# Vector_Body_Board_Schematic.net
KiCad netlist of a schematic drawn in EasyEDA
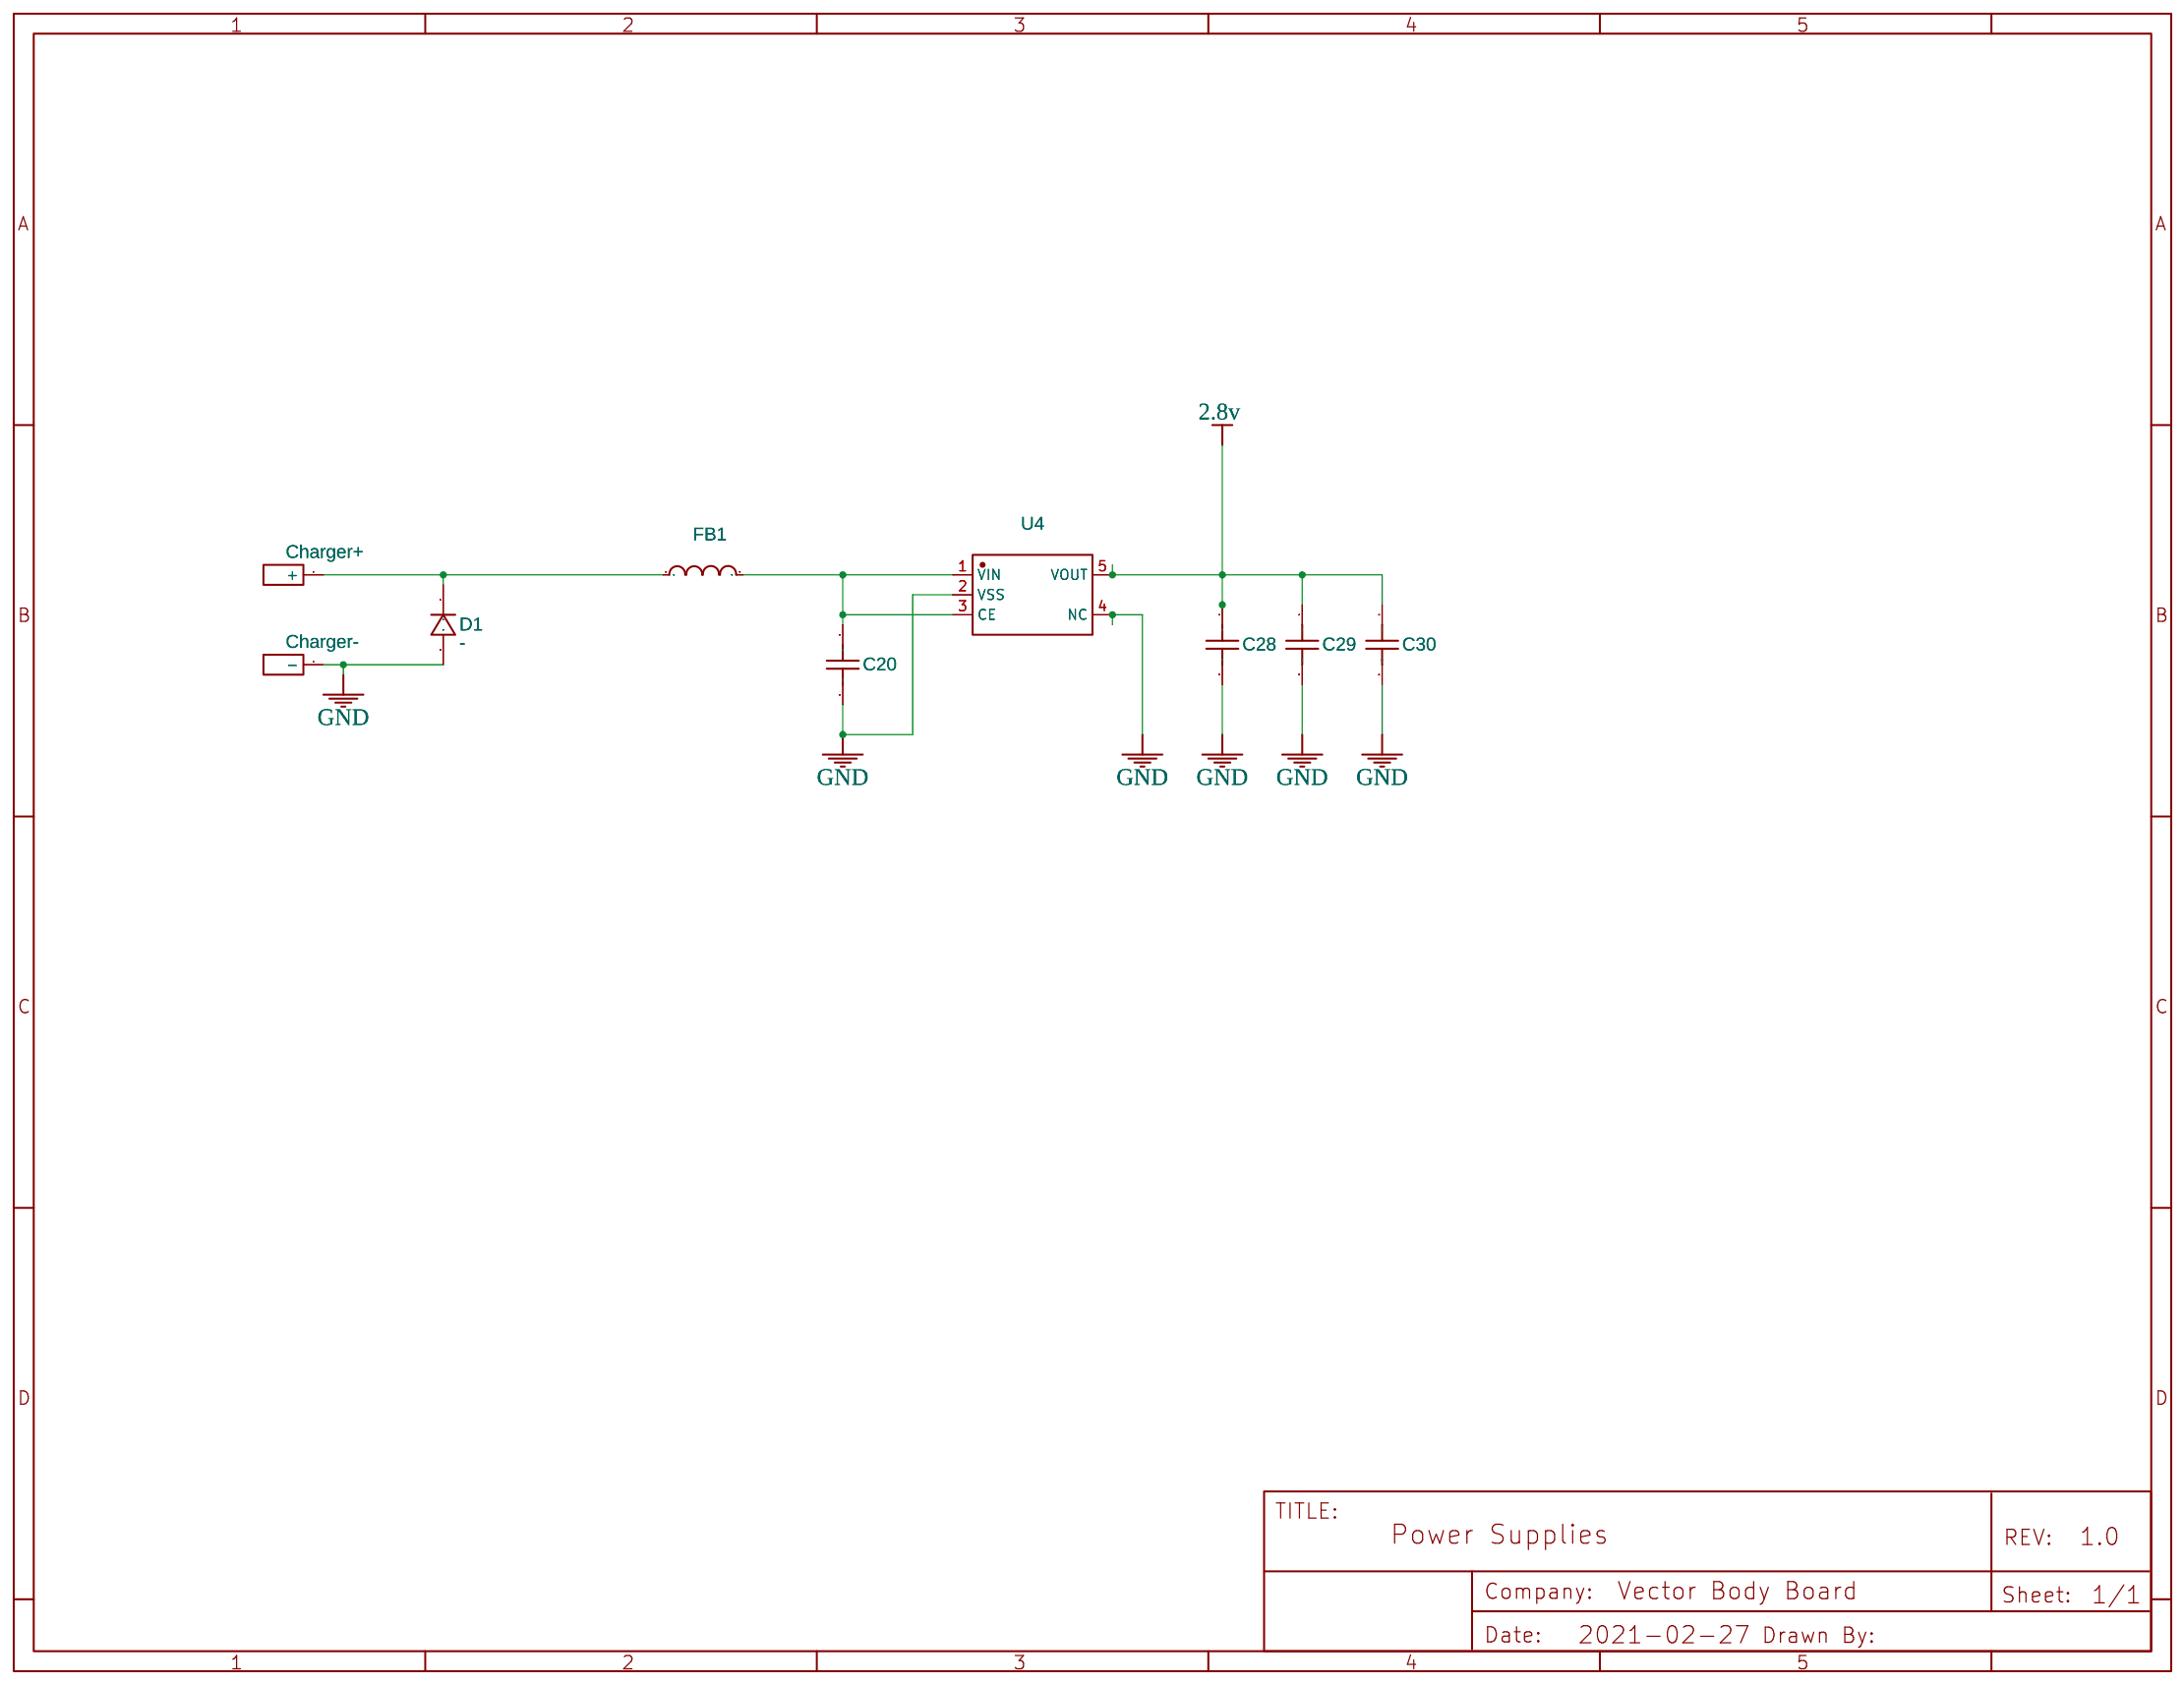
[diagram p0: Power Supply]
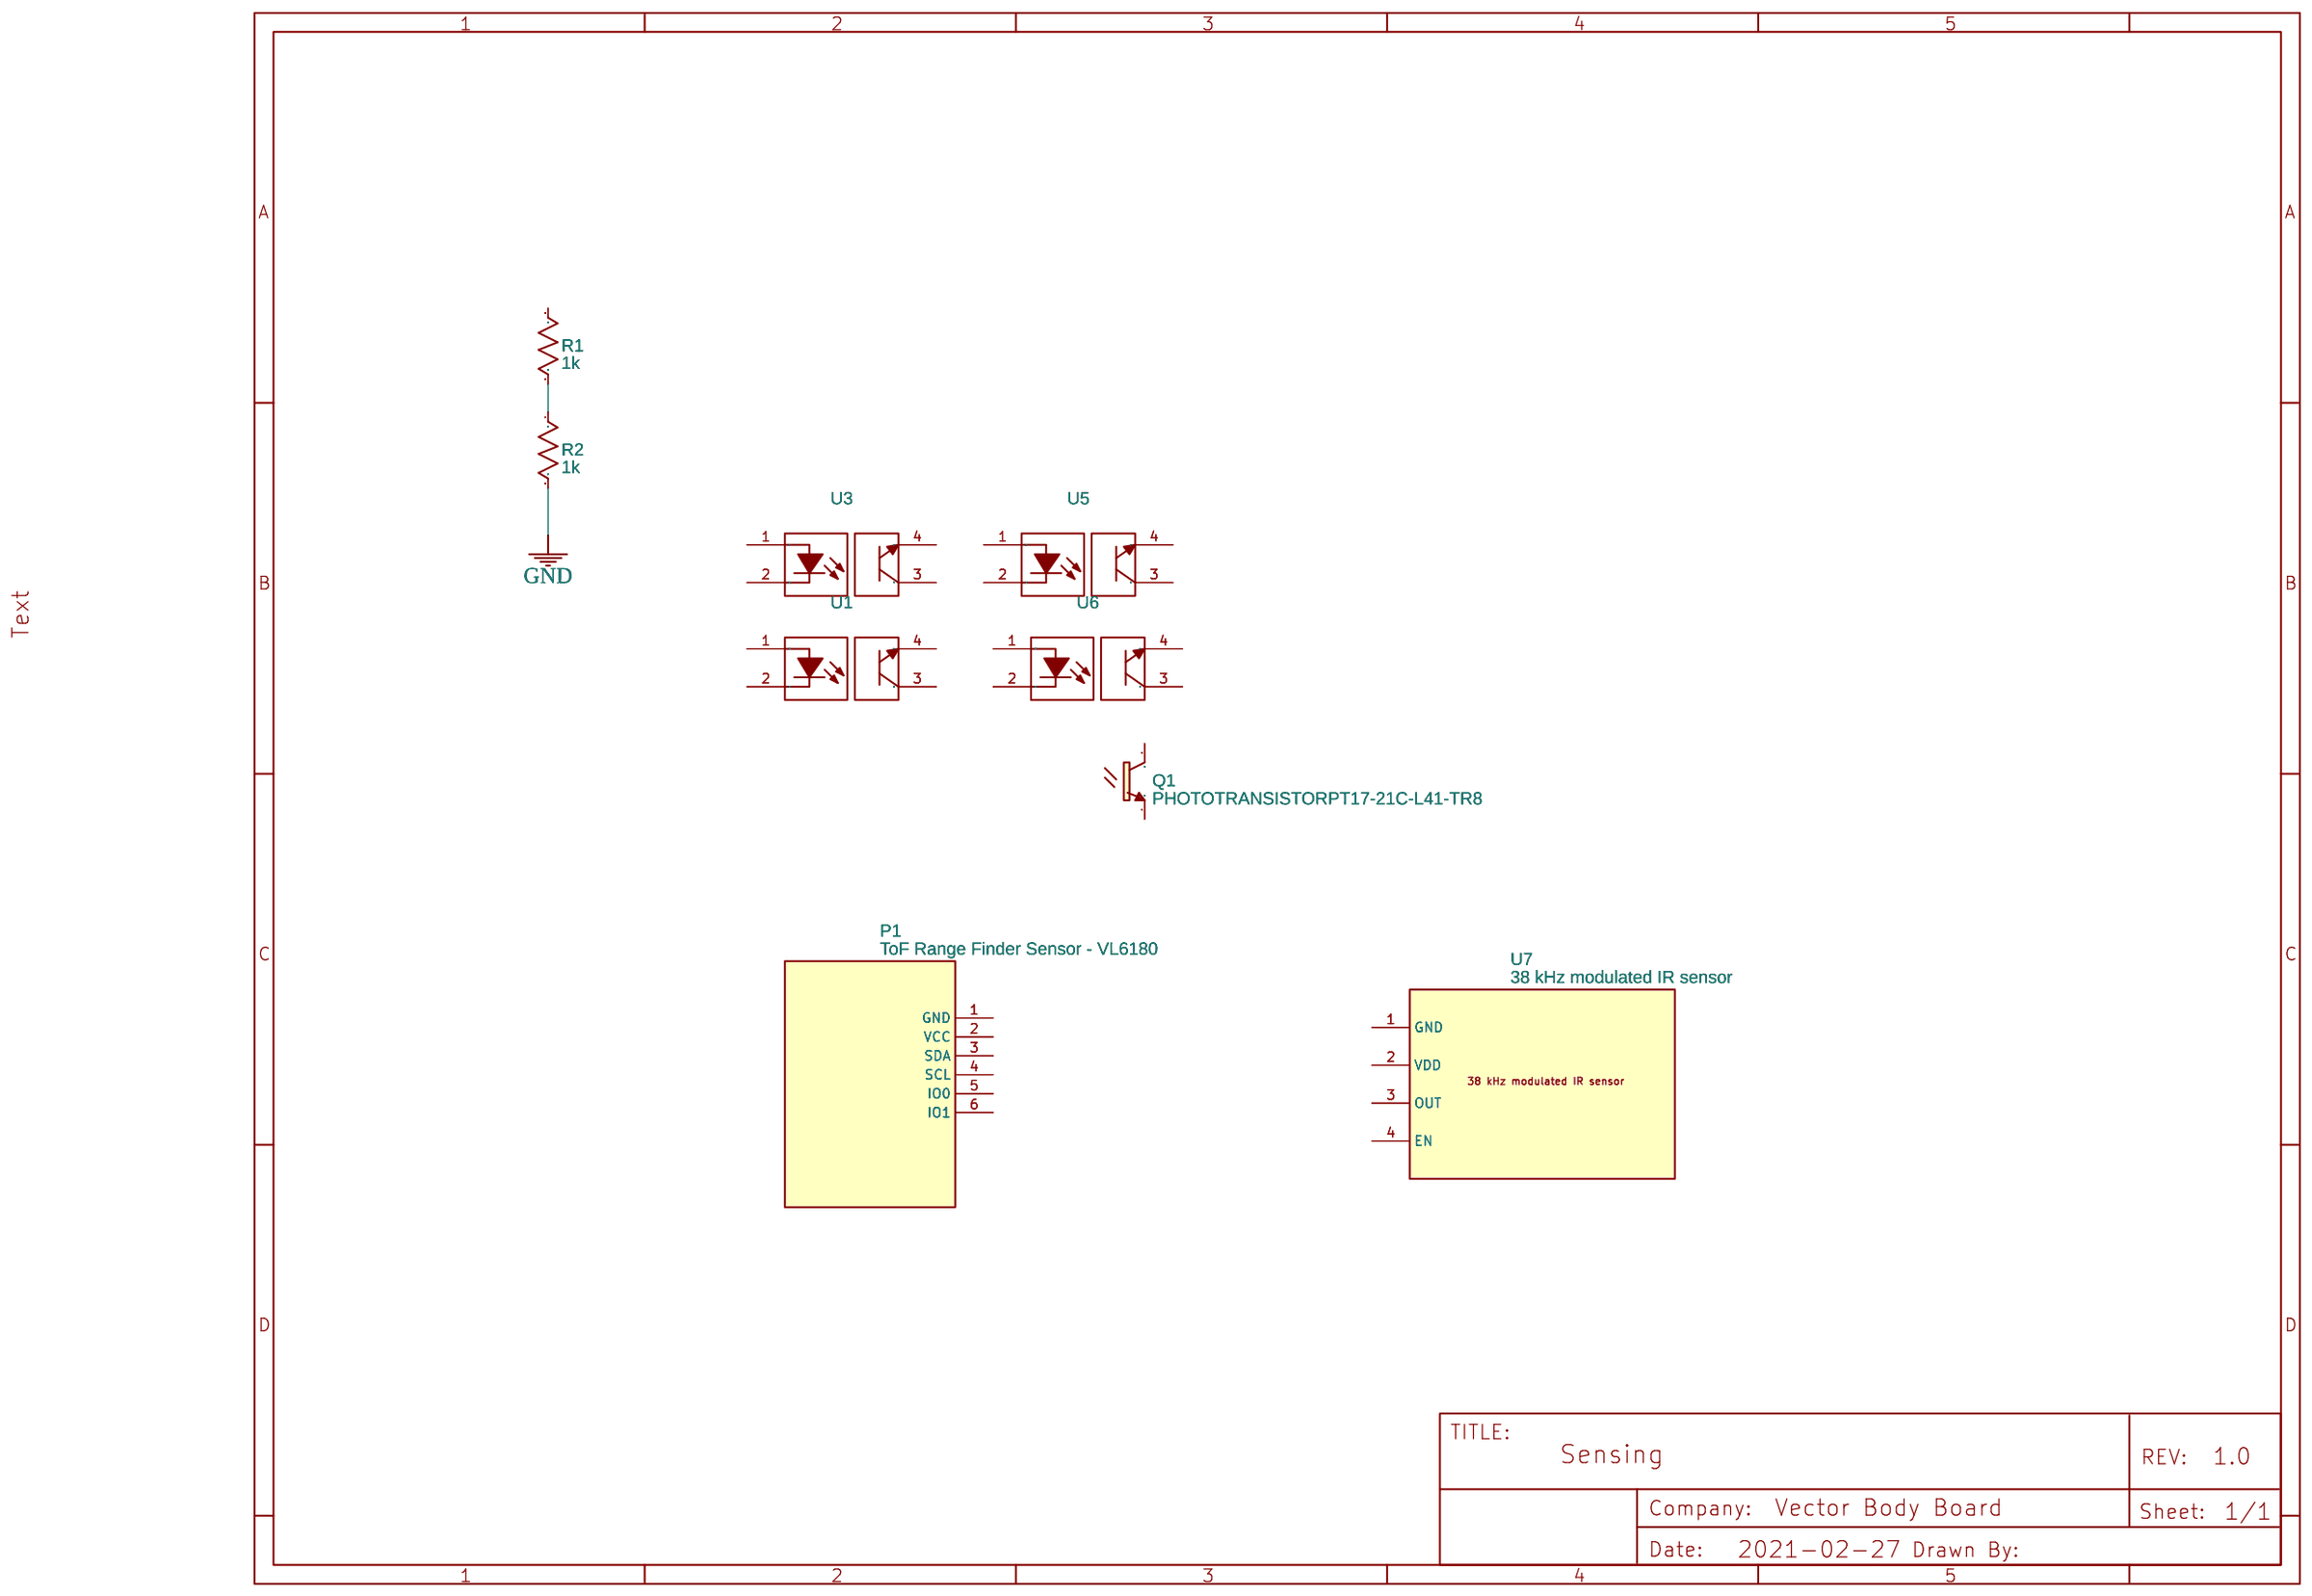
[diagram p1: Sensing]
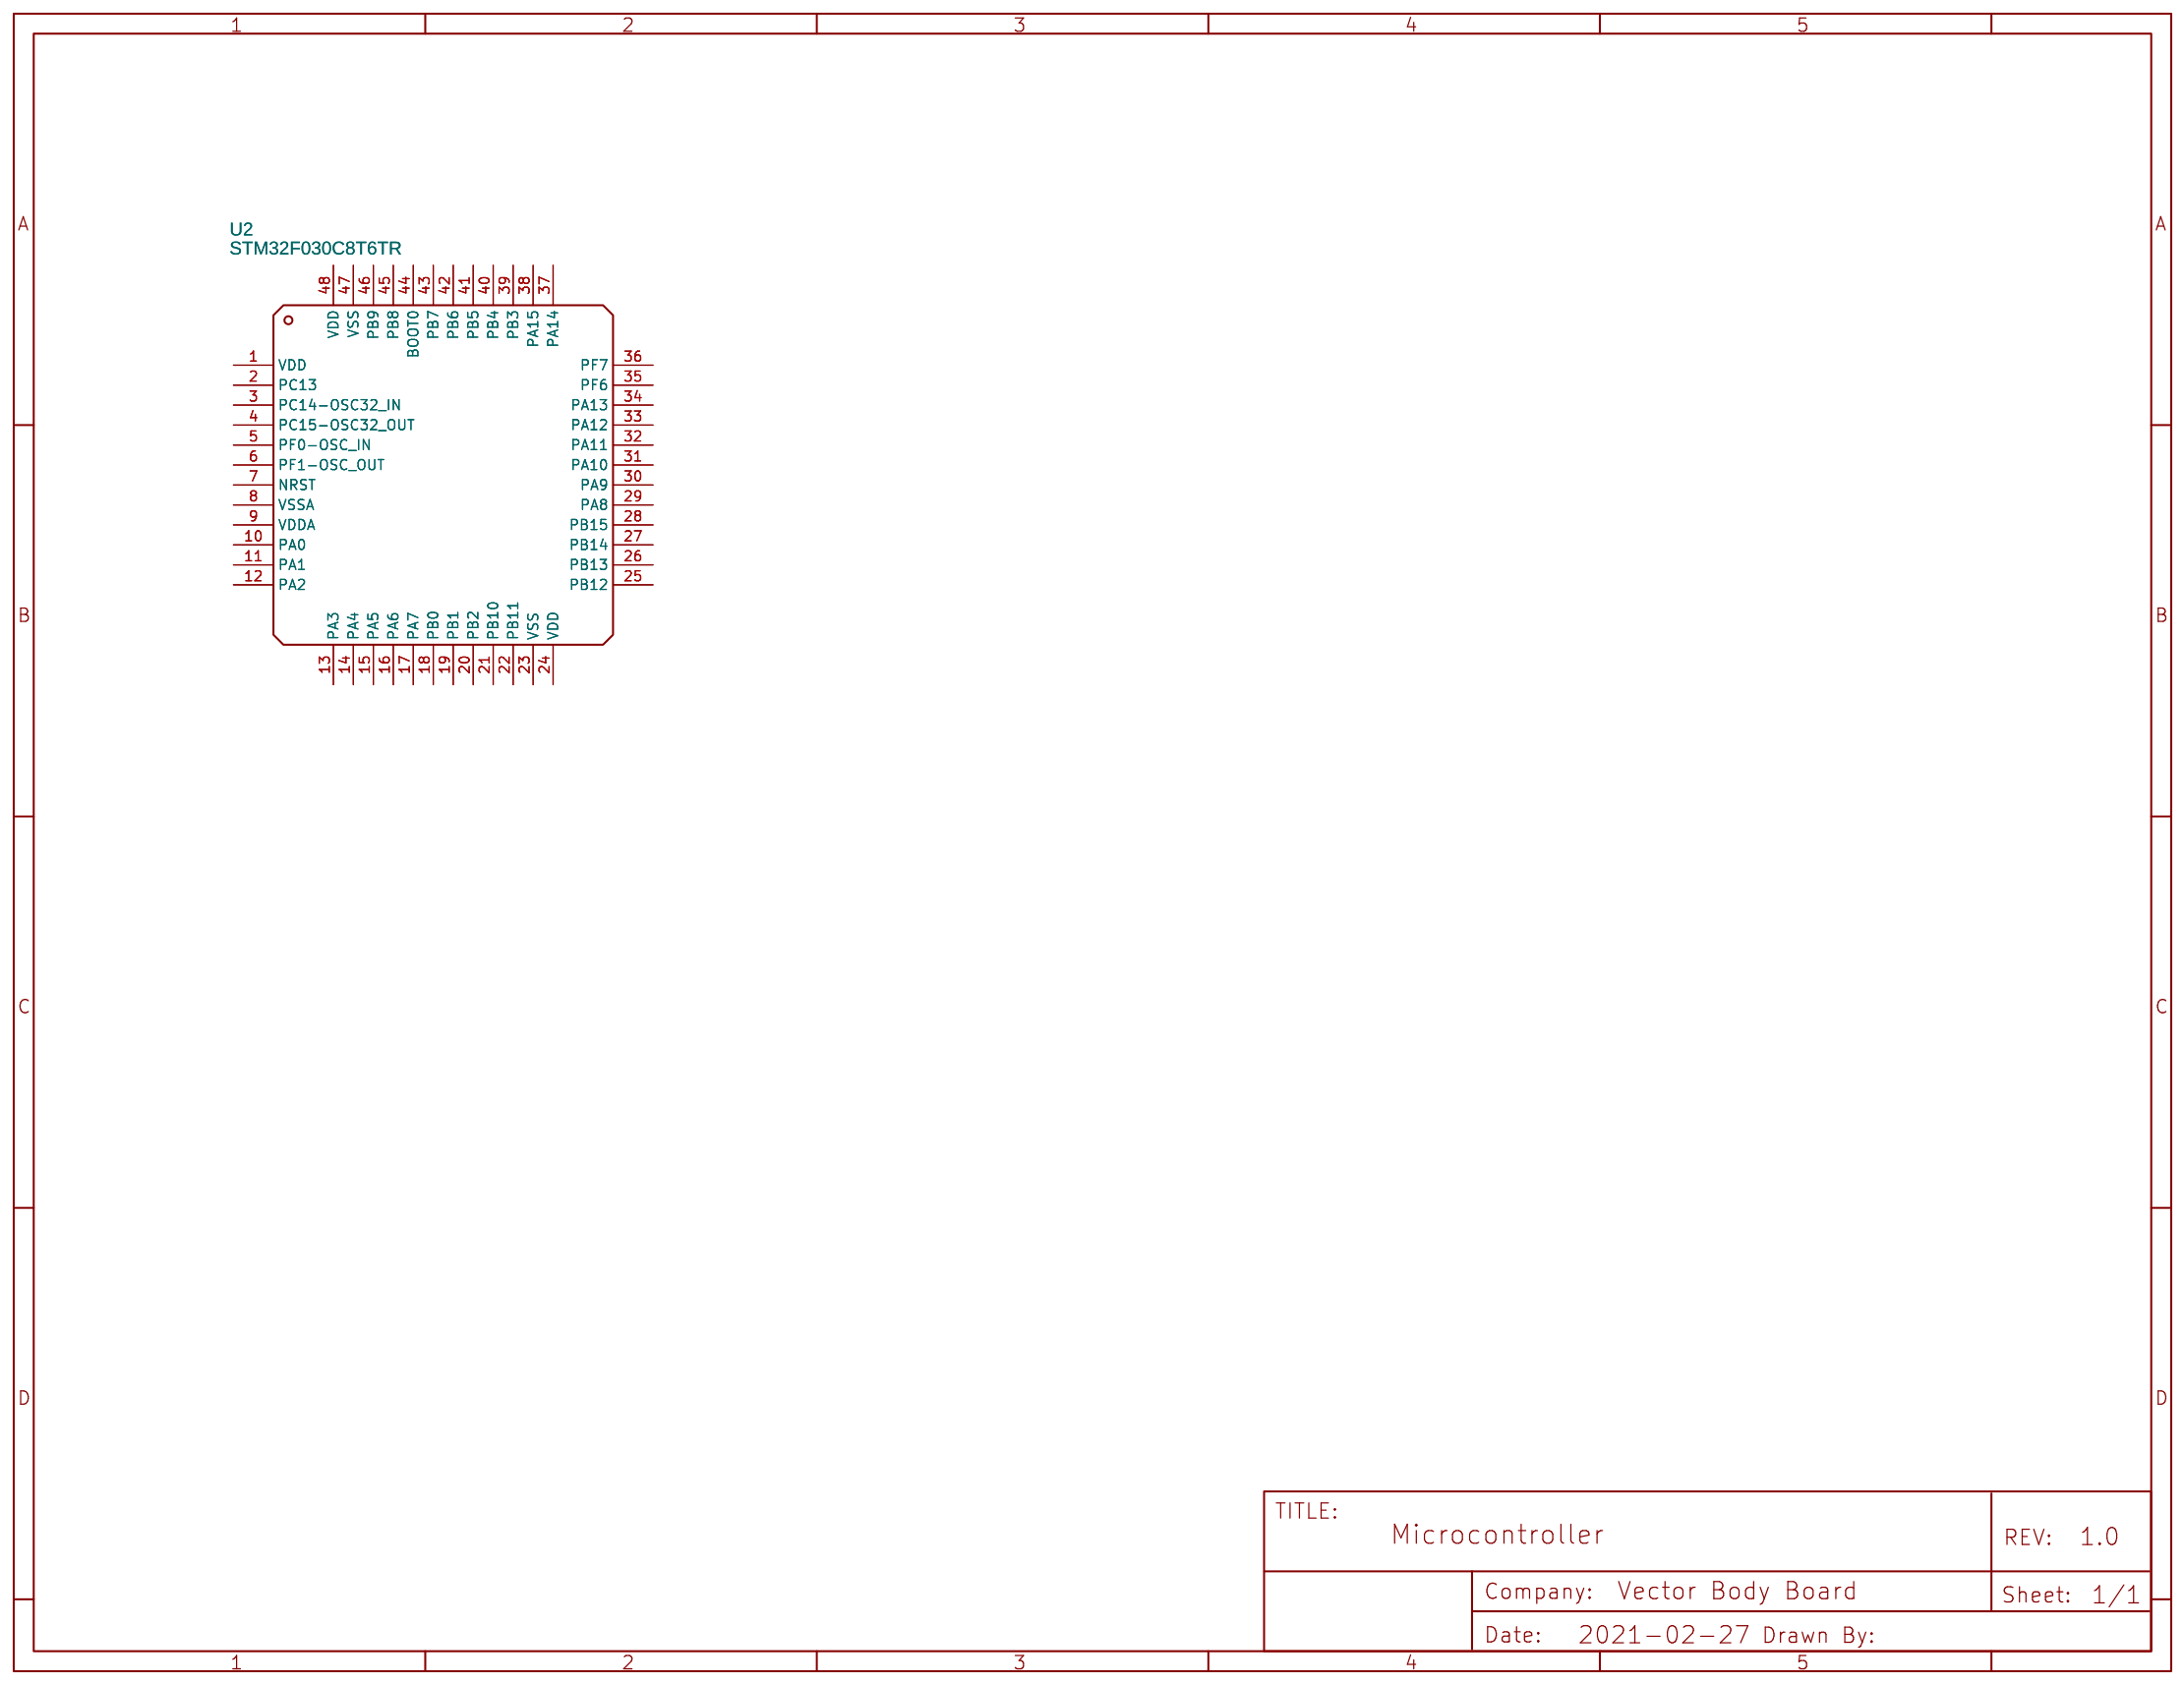
[diagram p2: Microcontroller]

(export (version "E")
  (design (tool "Eeschema 10.0.6"))
  (components
    (comp (ref "+")
      (value "Charger+")
      (fields (field (name "BOM_Supplier Part") "C81276"))
      (libsource (lib "") (part "HDR-M-2.54_1x1"))
    )
    (comp (ref "C20") (value "1u") (libsource (lib "") (part "C_0603_US")))
    (comp (ref "C28") (value "0.1u") (libsource (lib "") (part "C_0603_US")))
    (comp (ref "C29") (value "0.1u") (libsource (lib "") (part "C_0603_US")))
    (comp (ref "C30") (value "0.1u") (libsource (lib "") (part "C_0603_US")))
    (comp (ref "D1")
      (value "-")
      (fields (field (name "BOM_Manufacturer Part") "1N4007W") (field (name "BOM_Supplier Part") "C328592"))
      (libsource (lib "") (part "1N4007W"))
    )
    (comp (ref "FB1")
      (value "Straight-through")
      (fields
        (field (name "BOM_Manufacturer Part") "Straight-through beads")
        (field (name "BOM_Supplier Part") "C46030")
      )
      (libsource (lib "") (part "Straight-through beads"))
    )
    (comp (ref "J2") (value "Charger-") (libsource (lib "") (part "HDR-M-2.54_1x1_1")))
    (comp (ref "U4")
      (value "XC6204B282MR")
      (fields (field (name "BOM_Supplier Part") "C17012"))
      (libsource (lib "") (part "XC6204B282MR"))
    )
    (comp (ref "P1")
      (value "ToF Range Finder Sensor - VL6180")
      (fields (field (name "BOM_Supplier Part") "12587"))
      (libsource (lib "") (part "ToF Range Finder Sensor - VL6180"))
    )
    (comp (ref "Q1")
      (value "PHOTOTRANSISTORPT17-21C-L41-TR8")
      (libsource (lib "") (part "PHOTOTRANSISTORPT17-21C-L41-TR8"))
    )
    (comp (ref "R1") (value "1k") (libsource (lib "") (part "R_0603_US")))
    (comp (ref "R2") (value "1k") (libsource (lib "") (part "R_0603_US")))
    (comp (ref "U1")
      (value "H21A1")
      (fields (field (name "BOM_Supplier Part") "C90607"))
      (libsource (lib "") (part "H21A1"))
    )
    (comp (ref "U3")
      (value "H21A1")
      (fields (field (name "BOM_Supplier Part") "C90607"))
      (libsource (lib "") (part "H21A1"))
    )
    (comp (ref "U5")
      (value "H21A1")
      (fields (field (name "BOM_Supplier Part") "C90607"))
      (libsource (lib "") (part "H21A1"))
    )
    (comp (ref "U6")
      (value "H21A1")
      (fields (field (name "BOM_Supplier Part") "C90607"))
      (libsource (lib "") (part "H21A1"))
    )
    (comp (ref "U7")
      (value "38 kHz modulated IR sensor")
      (libsource (lib "") (part "38 kHz modulated IR sensor"))
    )
    (comp (ref "U2")
      (value "STM32F030C8T6TR")
      (fields (field (name "BOM_Supplier Part") "C40053"))
      (libsource (lib "") (part "STM32F030C8T6TR"))
    )
  )
  (nets
    (net (code "1") (name "2.8v") (class "Default")
      (node (ref "C28") (pin "1") (pinfunction "1_1") (pintype "unspecified"))
      (node (ref "C29") (pin "1") (pinfunction "1_1") (pintype "unspecified"))
      (node (ref "C30") (pin "1") (pinfunction "1_1") (pintype "unspecified"))
      (node (ref "U4") (pin "5") (pinfunction "VOUT_5") (pintype "unspecified"))
    )
    (net (code "2") (name "GND") (class "Default")
      (node (ref "C20") (pin "2") (pinfunction "2_2") (pintype "unspecified"))
      (node (ref "C28") (pin "2") (pinfunction "2_2") (pintype "unspecified"))
      (node (ref "C29") (pin "2") (pinfunction "2_2") (pintype "unspecified"))
      (node (ref "C30") (pin "2") (pinfunction "2_2") (pintype "unspecified"))
      (node (ref "D1") (pin "2") (pinfunction "2_2") (pintype "unspecified"))
      (node (ref "J2") (pin "1") (pinfunction "-_1") (pintype "input"))
      (node (ref "R2") (pin "2") (pinfunction "2_2") (pintype "unspecified"))
      (node (ref "U4") (pin "2") (pinfunction "VSS_2") (pintype "unspecified"))
      (node (ref "U4") (pin "4") (pinfunction "NC_4") (pintype "unspecified"))
    )
    (net (code "3") (name "Net-(+-+)") (class "Default")
      (node (ref "+") (pin "1") (pinfunction "+_1") (pintype "input"))
      (node (ref "D1") (pin "1") (pinfunction "1_1") (pintype "unspecified"))
      (node (ref "FB1") (pin "1") (pinfunction "1_1") (pintype "unspecified"))
    )
    (net (code "4") (name "Net-(R1-Pad2)") (class "Default")
      (node (ref "R1") (pin "2") (pinfunction "2_2") (pintype "unspecified"))
      (node (ref "R2") (pin "1") (pinfunction "1_1") (pintype "unspecified"))
    )
    (net (code "5") (name "Net-(U4-CE)") (class "Default")
      (node (ref "C20") (pin "1") (pinfunction "1_1") (pintype "unspecified"))
      (node (ref "FB1") (pin "2") (pinfunction "2_2") (pintype "unspecified"))
      (node (ref "U4") (pin "1") (pinfunction "VIN_1") (pintype "unspecified"))
      (node (ref "U4") (pin "3") (pinfunction "CE_3") (pintype "unspecified"))
    )
    (net (code "6") (name "unconnected-(P1-GND-Pad1)") (class "Default")
      (node (ref "P1") (pin "1") (pinfunction "GND_1") (pintype "unspecified"))
    )
    (net (code "7") (name "unconnected-(P1-IO0-Pad5)") (class "Default")
      (node (ref "P1") (pin "5") (pinfunction "IO0_5") (pintype "unspecified"))
    )
    (net (code "8") (name "unconnected-(P1-IO1-Pad6)") (class "Default")
      (node (ref "P1") (pin "6") (pinfunction "IO1_6") (pintype "unspecified"))
    )
    (net (code "9") (name "unconnected-(P1-SCL-Pad4)") (class "Default")
      (node (ref "P1") (pin "4") (pinfunction "SCL_4") (pintype "unspecified"))
    )
    (net (code "10") (name "unconnected-(P1-SDA-Pad3)") (class "Default")
      (node (ref "P1") (pin "3") (pinfunction "SDA_3") (pintype "unspecified"))
    )
    (net (code "11") (name "unconnected-(P1-VCC-Pad2)") (class "Default")
      (node (ref "P1") (pin "2") (pinfunction "VCC_2") (pintype "unspecified"))
    )
    (net (code "12") (name "unconnected-(Q1-PadC)") (class "Default")
      (node (ref "Q1") (pin "C") (pinfunction "C_C") (pintype "unspecified"))
    )
    (net (code "13") (name "unconnected-(Q1-PadE)") (class "Default")
      (node (ref "Q1") (pin "E") (pinfunction "E_E") (pintype "unspecified"))
    )
    (net (code "14") (name "unconnected-(R1-Pad1)") (class "Default")
      (node (ref "R1") (pin "1") (pinfunction "1_1") (pintype "unspecified"))
    )
    (net (code "15") (name "unconnected-(U1-Pad1)") (class "Default")
      (node (ref "U1") (pin "1") (pinfunction "1_1") (pintype "unspecified"))
    )
    (net (code "16") (name "unconnected-(U1-Pad2)") (class "Default")
      (node (ref "U1") (pin "2") (pinfunction "2_2") (pintype "unspecified"))
    )
    (net (code "17") (name "unconnected-(U1-Pad3)") (class "Default")
      (node (ref "U1") (pin "3") (pinfunction "3_3") (pintype "unspecified"))
    )
    (net (code "18") (name "unconnected-(U1-Pad4)") (class "Default")
      (node (ref "U1") (pin "4") (pinfunction "4_4") (pintype "unspecified"))
    )
    (net (code "19") (name "unconnected-(U2-BOOT0-Pad44)") (class "Default")
      (node (ref "U2") (pin "44") (pinfunction "BOOT0_44") (pintype "unspecified"))
    )
    (net (code "20") (name "unconnected-(U2-NRST-Pad7)") (class "Default")
      (node (ref "U2") (pin "7") (pinfunction "NRST_7") (pintype "unspecified"))
    )
    (net (code "21") (name "unconnected-(U2-PA0-Pad10)") (class "Default")
      (node (ref "U2") (pin "10") (pinfunction "PA0_10") (pintype "unspecified"))
    )
    (net (code "22") (name "unconnected-(U2-PA1-Pad11)") (class "Default")
      (node (ref "U2") (pin "11") (pinfunction "PA1_11") (pintype "unspecified"))
    )
    (net (code "23") (name "unconnected-(U2-PA2-Pad12)") (class "Default")
      (node (ref "U2") (pin "12") (pinfunction "PA2_12") (pintype "unspecified"))
    )
    (net (code "24") (name "unconnected-(U2-PA3-Pad13)") (class "Default")
      (node (ref "U2") (pin "13") (pinfunction "PA3_13") (pintype "unspecified"))
    )
    (net (code "25") (name "unconnected-(U2-PA4-Pad14)") (class "Default")
      (node (ref "U2") (pin "14") (pinfunction "PA4_14") (pintype "unspecified"))
    )
    (net (code "26") (name "unconnected-(U2-PA5-Pad15)") (class "Default")
      (node (ref "U2") (pin "15") (pinfunction "PA5_15") (pintype "unspecified"))
    )
    (net (code "27") (name "unconnected-(U2-PA6-Pad16)") (class "Default")
      (node (ref "U2") (pin "16") (pinfunction "PA6_16") (pintype "unspecified"))
    )
    (net (code "28") (name "unconnected-(U2-PA7-Pad17)") (class "Default")
      (node (ref "U2") (pin "17") (pinfunction "PA7_17") (pintype "unspecified"))
    )
    (net (code "29") (name "unconnected-(U2-PA8-Pad29)") (class "Default")
      (node (ref "U2") (pin "29") (pinfunction "PA8_29") (pintype "unspecified"))
    )
    (net (code "30") (name "unconnected-(U2-PA9-Pad30)") (class "Default")
      (node (ref "U2") (pin "30") (pinfunction "PA9_30") (pintype "unspecified"))
    )
    (net (code "31") (name "unconnected-(U2-PA10-Pad31)") (class "Default")
      (node (ref "U2") (pin "31") (pinfunction "PA10_31") (pintype "unspecified"))
    )
    (net (code "32") (name "unconnected-(U2-PA11-Pad32)") (class "Default")
      (node (ref "U2") (pin "32") (pinfunction "PA11_32") (pintype "unspecified"))
    )
    (net (code "33") (name "unconnected-(U2-PA12-Pad33)") (class "Default")
      (node (ref "U2") (pin "33") (pinfunction "PA12_33") (pintype "unspecified"))
    )
    (net (code "34") (name "unconnected-(U2-PA13-Pad34)") (class "Default")
      (node (ref "U2") (pin "34") (pinfunction "PA13_34") (pintype "unspecified"))
    )
    (net (code "35") (name "unconnected-(U2-PA14-Pad37)") (class "Default")
      (node (ref "U2") (pin "37") (pinfunction "PA14_37") (pintype "unspecified"))
    )
    (net (code "36") (name "unconnected-(U2-PA15-Pad38)") (class "Default")
      (node (ref "U2") (pin "38") (pinfunction "PA15_38") (pintype "unspecified"))
    )
    (net (code "37") (name "unconnected-(U2-PB0-Pad18)") (class "Default")
      (node (ref "U2") (pin "18") (pinfunction "PB0_18") (pintype "unspecified"))
    )
    (net (code "38") (name "unconnected-(U2-PB1-Pad19)") (class "Default")
      (node (ref "U2") (pin "19") (pinfunction "PB1_19") (pintype "unspecified"))
    )
    (net (code "39") (name "unconnected-(U2-PB2-Pad20)") (class "Default")
      (node (ref "U2") (pin "20") (pinfunction "PB2_20") (pintype "unspecified"))
    )
    (net (code "40") (name "unconnected-(U2-PB3-Pad39)") (class "Default")
      (node (ref "U2") (pin "39") (pinfunction "PB3_39") (pintype "unspecified"))
    )
    (net (code "41") (name "unconnected-(U2-PB4-Pad40)") (class "Default")
      (node (ref "U2") (pin "40") (pinfunction "PB4_40") (pintype "unspecified"))
    )
    (net (code "42") (name "unconnected-(U2-PB5-Pad41)") (class "Default")
      (node (ref "U2") (pin "41") (pinfunction "PB5_41") (pintype "unspecified"))
    )
    (net (code "43") (name "unconnected-(U2-PB6-Pad42)") (class "Default")
      (node (ref "U2") (pin "42") (pinfunction "PB6_42") (pintype "unspecified"))
    )
    (net (code "44") (name "unconnected-(U2-PB7-Pad43)") (class "Default")
      (node (ref "U2") (pin "43") (pinfunction "PB7_43") (pintype "unspecified"))
    )
    (net (code "45") (name "unconnected-(U2-PB8-Pad45)") (class "Default")
      (node (ref "U2") (pin "45") (pinfunction "PB8_45") (pintype "unspecified"))
    )
    (net (code "46") (name "unconnected-(U2-PB9-Pad46)") (class "Default")
      (node (ref "U2") (pin "46") (pinfunction "PB9_46") (pintype "unspecified"))
    )
    (net (code "47") (name "unconnected-(U2-PB10-Pad21)") (class "Default")
      (node (ref "U2") (pin "21") (pinfunction "PB10_21") (pintype "unspecified"))
    )
    (net (code "48") (name "unconnected-(U2-PB11-Pad22)") (class "Default")
      (node (ref "U2") (pin "22") (pinfunction "PB11_22") (pintype "unspecified"))
    )
    (net (code "49") (name "unconnected-(U2-PB12-Pad25)") (class "Default")
      (node (ref "U2") (pin "25") (pinfunction "PB12_25") (pintype "unspecified"))
    )
    (net (code "50") (name "unconnected-(U2-PB13-Pad26)") (class "Default")
      (node (ref "U2") (pin "26") (pinfunction "PB13_26") (pintype "unspecified"))
    )
    (net (code "51") (name "unconnected-(U2-PB14-Pad27)") (class "Default")
      (node (ref "U2") (pin "27") (pinfunction "PB14_27") (pintype "unspecified"))
    )
    (net (code "52") (name "unconnected-(U2-PB15-Pad28)") (class "Default")
      (node (ref "U2") (pin "28") (pinfunction "PB15_28") (pintype "unspecified"))
    )
    (net (code "53") (name "unconnected-(U2-PC13-Pad2)") (class "Default")
      (node (ref "U2") (pin "2") (pinfunction "PC13_2") (pintype "unspecified"))
    )
    (net (code "54") (name "unconnected-(U2-PC14-OSC32_IN-Pad3)") (class "Default")
      (node (ref "U2") (pin "3") (pinfunction "PC14-OSC32_IN_3") (pintype "unspecified"))
    )
    (net (code "55") (name "unconnected-(U2-PC15-OSC32_OUT-Pad4)") (class "Default")
      (node (ref "U2") (pin "4") (pinfunction "PC15-OSC32_OUT_4") (pintype "unspecified"))
    )
    (net (code "56") (name "unconnected-(U2-PF0-OSC_IN-Pad5)") (class "Default")
      (node (ref "U2") (pin "5") (pinfunction "PF0-OSC_IN_5") (pintype "unspecified"))
    )
    (net (code "57") (name "unconnected-(U2-PF1-OSC_OUT-Pad6)") (class "Default")
      (node (ref "U2") (pin "6") (pinfunction "PF1-OSC_OUT_6") (pintype "unspecified"))
    )
    (net (code "58") (name "unconnected-(U2-PF6-Pad35)") (class "Default")
      (node (ref "U2") (pin "35") (pinfunction "PF6_35") (pintype "unspecified"))
    )
    (net (code "59") (name "unconnected-(U2-PF7-Pad36)") (class "Default")
      (node (ref "U2") (pin "36") (pinfunction "PF7_36") (pintype "unspecified"))
    )
    (net (code "60") (name "unconnected-(U2-VDD-Pad1)") (class "Default")
      (node (ref "U2") (pin "1") (pinfunction "VDD_1") (pintype "unspecified"))
    )
    (net (code "61") (name "unconnected-(U2-VDD-Pad24)") (class "Default")
      (node (ref "U2") (pin "24") (pinfunction "VDD_24") (pintype "unspecified"))
    )
    (net (code "62") (name "unconnected-(U2-VDD-Pad48)") (class "Default")
      (node (ref "U2") (pin "48") (pinfunction "VDD_48") (pintype "unspecified"))
    )
    (net (code "63") (name "unconnected-(U2-VDDA-Pad9)") (class "Default")
      (node (ref "U2") (pin "9") (pinfunction "VDDA_9") (pintype "unspecified"))
    )
    (net (code "64") (name "unconnected-(U2-VSS-Pad23)") (class "Default")
      (node (ref "U2") (pin "23") (pinfunction "VSS_23") (pintype "unspecified"))
    )
    (net (code "65") (name "unconnected-(U2-VSS-Pad47)") (class "Default")
      (node (ref "U2") (pin "47") (pinfunction "VSS_47") (pintype "unspecified"))
    )
    (net (code "66") (name "unconnected-(U2-VSSA-Pad8)") (class "Default")
      (node (ref "U2") (pin "8") (pinfunction "VSSA_8") (pintype "unspecified"))
    )
    (net (code "67") (name "unconnected-(U3-Pad1)") (class "Default")
      (node (ref "U3") (pin "1") (pinfunction "1_1") (pintype "unspecified"))
    )
    (net (code "68") (name "unconnected-(U3-Pad2)") (class "Default")
      (node (ref "U3") (pin "2") (pinfunction "2_2") (pintype "unspecified"))
    )
    (net (code "69") (name "unconnected-(U3-Pad3)") (class "Default")
      (node (ref "U3") (pin "3") (pinfunction "3_3") (pintype "unspecified"))
    )
    (net (code "70") (name "unconnected-(U3-Pad4)") (class "Default")
      (node (ref "U3") (pin "4") (pinfunction "4_4") (pintype "unspecified"))
    )
    (net (code "71") (name "unconnected-(U5-Pad1)") (class "Default")
      (node (ref "U5") (pin "1") (pinfunction "1_1") (pintype "unspecified"))
    )
    (net (code "72") (name "unconnected-(U5-Pad2)") (class "Default")
      (node (ref "U5") (pin "2") (pinfunction "2_2") (pintype "unspecified"))
    )
    (net (code "73") (name "unconnected-(U5-Pad3)") (class "Default")
      (node (ref "U5") (pin "3") (pinfunction "3_3") (pintype "unspecified"))
    )
    (net (code "74") (name "unconnected-(U5-Pad4)") (class "Default")
      (node (ref "U5") (pin "4") (pinfunction "4_4") (pintype "unspecified"))
    )
    (net (code "75") (name "unconnected-(U6-Pad1)") (class "Default")
      (node (ref "U6") (pin "1") (pinfunction "1_1") (pintype "unspecified"))
    )
    (net (code "76") (name "unconnected-(U6-Pad2)") (class "Default")
      (node (ref "U6") (pin "2") (pinfunction "2_2") (pintype "unspecified"))
    )
    (net (code "77") (name "unconnected-(U6-Pad3)") (class "Default")
      (node (ref "U6") (pin "3") (pinfunction "3_3") (pintype "unspecified"))
    )
    (net (code "78") (name "unconnected-(U6-Pad4)") (class "Default")
      (node (ref "U6") (pin "4") (pinfunction "4_4") (pintype "unspecified"))
    )
    (net (code "79") (name "unconnected-(U7-EN-Pad4)") (class "Default")
      (node (ref "U7") (pin "4") (pinfunction "EN_4") (pintype "unspecified"))
    )
    (net (code "80") (name "unconnected-(U7-GND-Pad1)") (class "Default")
      (node (ref "U7") (pin "1") (pinfunction "GND_1") (pintype "unspecified"))
    )
    (net (code "81") (name "unconnected-(U7-OUT-Pad3)") (class "Default")
      (node (ref "U7") (pin "3") (pinfunction "OUT_3") (pintype "unspecified"))
    )
    (net (code "82") (name "unconnected-(U7-VDD-Pad2)") (class "Default")
      (node (ref "U7") (pin "2") (pinfunction "VDD_2") (pintype "unspecified"))
    )
  )
)
